# power_supply_sch.net
KiCad netlist of a schematic drawn in EAGLE
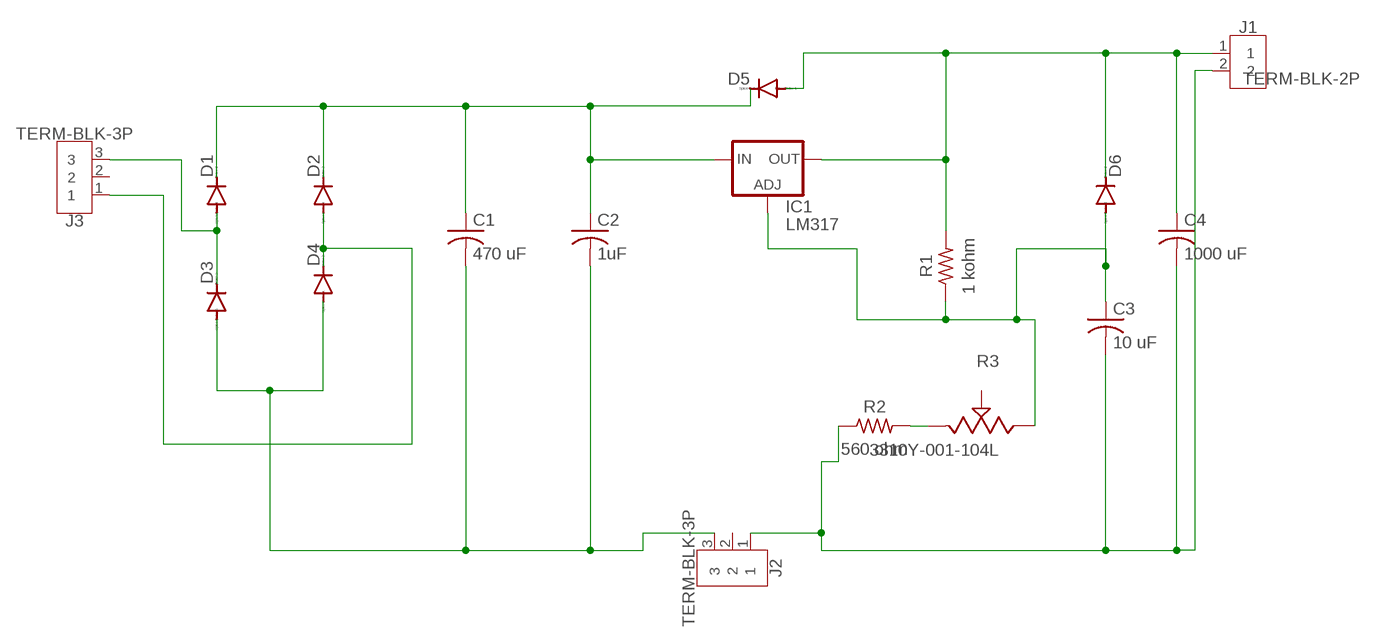
[diagram p0: schematic, sheet 1]

(export (version "E")
  (design (tool "Eeschema 10.0.6"))
  (components
    (comp (ref "C1")
      (value "470 uF")
      (footprint "eagle-import:CAPRD550W60D1025H1250B")
      (libsource (lib "eagle-import") (part "C-USRADIAL-12.5MM-DIA_"))
    )
    (comp (ref "C2")
      (value "1uF")
      (footprint "eagle-import:CAPRD550W60D1025H1250B")
      (libsource (lib "eagle-import") (part "C-USRADIAL-12.5MM-DIA_"))
    )
    (comp (ref "C3")
      (value "10 uF")
      (footprint "eagle-import:CAPRD550W60D1025H1250B")
      (libsource (lib "eagle-import") (part "C-USRADIAL-12.5MM-DIA_"))
    )
    (comp (ref "C4")
      (value "1000 uF")
      (footprint "eagle-import:CAPRD550W60D1025H1250B")
      (libsource (lib "eagle-import") (part "C-USRADIAL-12.5MM-DIA_"))
    )
    (comp (ref "D1")
      (value "1N4004")
      (footprint "eagle-import:DO41-10")
      (libsource (lib "eagle-import") (part "1N4004"))
    )
    (comp (ref "D2")
      (value "1N4004")
      (footprint "eagle-import:DO41-10")
      (libsource (lib "eagle-import") (part "1N4004"))
    )
    (comp (ref "D3")
      (value "1N4004")
      (footprint "eagle-import:DO41-10")
      (libsource (lib "eagle-import") (part "1N4004"))
    )
    (comp (ref "D4")
      (value "1N4004")
      (footprint "eagle-import:DO41-10")
      (libsource (lib "eagle-import") (part "1N4004"))
    )
    (comp (ref "D5")
      (value "1N4004")
      (footprint "eagle-import:DO41-10")
      (libsource (lib "eagle-import") (part "1N4004"))
    )
    (comp (ref "D6")
      (value "1N4004")
      (footprint "eagle-import:DO41-10")
      (libsource (lib "eagle-import") (part "1N4004"))
    )
    (comp (ref "IC1")
      (value "LM317")
      (footprint "eagle-import:317TL")
      (libsource (lib "eagle-import") (part "LM317TL"))
    )
    (comp (ref "J1")
      (value "TERM-BLK-2P")
      (footprint "eagle-import:TERMBLK_508-2N")
      (fields (field (name "MANUFACTURER") "TE Connectivity AMP Connectors") (field (name "MPN") "282837-2"))
      (libsource (lib "eagle-import") (part "2828XX-2282837-2"))
    )
    (comp (ref "J2")
      (value "TERM-BLK-3P")
      (footprint "eagle-import:TERMBLK_508-3N")
      (fields (field (name "MANUFACTURER") "TE Connectivity") (field (name "MPN") "282837-3"))
      (libsource (lib "eagle-import") (part "2828XX-3282837-3"))
    )
    (comp (ref "J3")
      (value "TERM-BLK-3P")
      (footprint "eagle-import:TERMBLK_508-3N")
      (fields (field (name "MANUFACTURER") "TE Connectivity") (field (name "MPN") "282837-3"))
      (libsource (lib "eagle-import") (part "2828XX-3282837-3"))
    )
    (comp (ref "R1")
      (value "1 kohm")
      (footprint "eagle-import:RESAD724W46L381D178B")
      (libsource (lib "eagle-import") (part "R-USAXIAL-7.2MM-PITCH_"))
    )
    (comp (ref "R2")
      (value "560 ohm")
      (footprint "eagle-import:RESAD724W46L381D178B")
      (libsource (lib "eagle-import") (part "R-USAXIAL-7.2MM-PITCH_"))
    )
    (comp (ref "R3")
      (value "3310Y-001-104L")
      (footprint "eagle-import:3310Y-001-104L-ND")
      (fields
        (field (name "DIGIKEY_PARTNO") "3310Y-001-104L-ND")
        (field (name "MANUFACTURER") "Bourns Inc.")
        (field (name "CREATED_BY") " PCBLayout.com")
      )
      (libsource (lib "eagle-import") (part "3310Y-001-104L"))
    )
  )
  (nets
    (net (code "1") (name "Net-(C1-Pad2)") (class "Default")
      (node (ref "C1") (pin "2") (pinfunction "2_2") (pintype "passive"))
      (node (ref "C2") (pin "2") (pinfunction "2_2") (pintype "passive"))
      (node (ref "D3") (pin "A") (pinfunction "A_A") (pintype "passive"))
      (node (ref "D4") (pin "A") (pinfunction "A_A") (pintype "passive"))
      (node (ref "J2") (pin "3") (pinfunction "3_3") (pintype "bidirectional"))
    )
    (net (code "2") (name "Net-(C3-Pad2)") (class "Default")
      (node (ref "C3") (pin "2") (pinfunction "2_2") (pintype "passive"))
      (node (ref "C4") (pin "2") (pinfunction "2_2") (pintype "passive"))
      (node (ref "J1") (pin "2") (pinfunction "2_2") (pintype "bidirectional"))
      (node (ref "J2") (pin "1") (pinfunction "1_1") (pintype "bidirectional"))
      (node (ref "R2") (pin "1") (pinfunction "1_1") (pintype "passive"))
    )
    (net (code "3") (name "Net-(D1-PadA)") (class "Default")
      (node (ref "D1") (pin "A") (pinfunction "A_A") (pintype "passive"))
      (node (ref "D3") (pin "C") (pinfunction "C_C") (pintype "passive"))
      (node (ref "J3") (pin "3") (pinfunction "3_3") (pintype "bidirectional"))
    )
    (net (code "4") (name "Net-(D2-PadA)") (class "Default")
      (node (ref "D2") (pin "A") (pinfunction "A_A") (pintype "passive"))
      (node (ref "D4") (pin "C") (pinfunction "C_C") (pintype "passive"))
      (node (ref "J3") (pin "1") (pinfunction "1_1") (pintype "bidirectional"))
    )
    (net (code "5") (name "Net-(IC1-ADJ)") (class "Default")
      (node (ref "C3") (pin "1") (pinfunction "1_1") (pintype "passive"))
      (node (ref "D6") (pin "A") (pinfunction "A_A") (pintype "passive"))
      (node (ref "IC1") (pin "1") (pinfunction "ADJ_1") (pintype "input"))
      (node (ref "R1") (pin "1") (pinfunction "1_1") (pintype "passive"))
      (node (ref "R3") (pin "3") (pinfunction "3_3") (pintype "passive"))
    )
    (net (code "6") (name "Net-(IC1-IN)") (class "Default")
      (node (ref "C1") (pin "1") (pinfunction "1_1") (pintype "passive"))
      (node (ref "C2") (pin "1") (pinfunction "1_1") (pintype "passive"))
      (node (ref "D1") (pin "C") (pinfunction "C_C") (pintype "passive"))
      (node (ref "D2") (pin "C") (pinfunction "C_C") (pintype "passive"))
      (node (ref "D5") (pin "C") (pinfunction "C_C") (pintype "passive"))
      (node (ref "IC1") (pin "3") (pinfunction "IN_3") (pintype "input"))
    )
    (net (code "7") (name "Net-(IC1-OUT)") (class "Default")
      (node (ref "C4") (pin "1") (pinfunction "1_1") (pintype "passive"))
      (node (ref "D5") (pin "A") (pinfunction "A_A") (pintype "passive"))
      (node (ref "D6") (pin "C") (pinfunction "C_C") (pintype "passive"))
      (node (ref "IC1") (pin "2") (pinfunction "OUT_2") (pintype "passive"))
      (node (ref "J1") (pin "1") (pinfunction "1_1") (pintype "bidirectional"))
      (node (ref "R1") (pin "2") (pinfunction "2_2") (pintype "passive"))
    )
    (net (code "8") (name "Net-(R2-Pad2)") (class "Default")
      (node (ref "R2") (pin "2") (pinfunction "2_2") (pintype "passive"))
      (node (ref "R3") (pin "1") (pinfunction "1_1") (pintype "passive"))
    )
    (net (code "9") (name "unconnected-(J2-Pad2)") (class "Default")
      (node (ref "J2") (pin "2") (pinfunction "2_2") (pintype "bidirectional"))
    )
    (net (code "10") (name "unconnected-(J3-Pad2)") (class "Default")
      (node (ref "J3") (pin "2") (pinfunction "2_2") (pintype "bidirectional"))
    )
    (net (code "11") (name "unconnected-(R3-Pad2)") (class "Default")
      (node (ref "R3") (pin "2") (pinfunction "2_2") (pintype "passive"))
    )
  )
)
